# VoltageSensing.net
KiCad netlist of a schematic drawn in Altium Designer
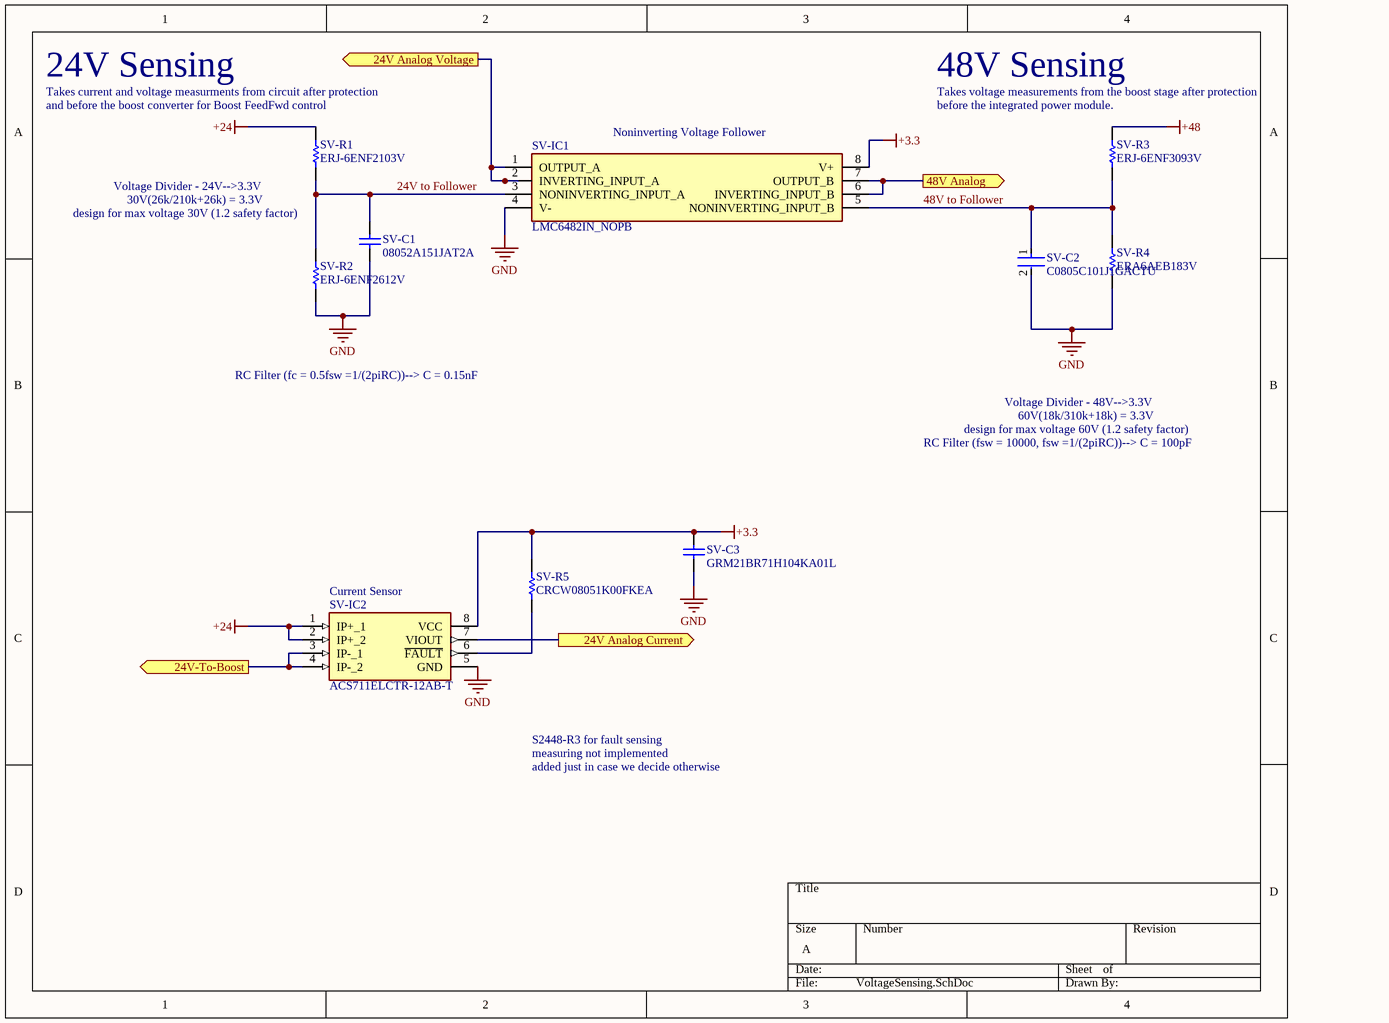
[diagram p0: VoltageSensing.SchDoc]

(export (version "E")
  (design (tool "Eeschema 10.0.6"))
  (components
    (comp (ref "SV-C1")
      (value "08052A151JAT2A")
      (footprint "CAPC2013X140X50ML20T25")
      (fields (field (name "MANUFACTURER") "AVX Interconnect / Elco"))
      (libsource (lib "Altium Content Vault") (part "CAP"))
    )
    (comp (ref "SV-C2")
      (value "C0805C101J1GACTU")
      (footprint "FP-C0805C-DN-MFG")
      (description "CAP CER 100PF 100V C0G/NP0 0805")
      (fields
        (field (name "MANUFACTURER") "KEMET")
        (field (name "OCTOPART") "https://octopart.com/c0805c101j1gactu-kemet-123666")
      )
      (libsource (lib "Altium Content Vault") (part "b4654b650e69147ec39a6b967a45e02"))
    )
    (comp (ref "SV-C3")
      (value "GRM21BR71H104KA01L")
      (footprint "CAPC2013X135X45ML10T25")
      (description "Chip Capacitor, 0.1 uF, +/- 10%, 50 V, -55 to 125 degC, 0805 (2012 Metric), RoHS, Tape and Reel")
      (fields (field (name "VOLTAGE") "50V") (field (name "TOLERANCE") "10%"))
      (libsource (lib "Altium Content Vault") (part "CAP-NP-2"))
    )
    (comp (ref "SV-IC1")
      (value "LMC6482IN_NOPB")
      (footprint "SamacSys:DIP794W53P254L959H508Q8N")
      (description "Integrated Circuit")
      (fields
        (field (name "MANUFACTURER_PART_NUMBER") "LMC6482IN/NOPB")
        (field (name "MOUSER PART NUMBER") "926-LMC6482IN/NOPB")
      )
      (libsource (lib "*") (part "LMC6482IN_NOPB"))
    )
    (comp (ref "SV-IC2")
      (value "ACS711ELCTR-12AB-T")
      (footprint "SamacSys:SOIC127P600X175-8N")
      (description "Integrated Circuit")
      (libsource (lib "*") (part "ACS711ELCTR-12AB-T"))
    )
    (comp (ref "SV-R1")
      (value "ERJ-6ENF2103V")
      (footprint "RESC2013X70X40NL20T20")
      (fields (field (name "MANUFACTURER") "Panasonic"))
      (libsource (lib "Altium Content Vault") (part "RES"))
    )
    (comp (ref "SV-R2")
      (value "ERJ-6ENF2612V")
      (footprint "RESC2013X70X40NL20T20")
      (fields (field (name "MANUFACTURER") "Panasonic"))
      (libsource (lib "Altium Content Vault") (part "RES"))
    )
    (comp (ref "SV-R3")
      (value "ERJ-6ENF3093V")
      (footprint "RESC2013X70X40NL20T20")
      (fields (field (name "MANUFACTURER") "Panasonic"))
      (libsource (lib "Altium Content Vault") (part "RES"))
    )
    (comp (ref "SV-R4")
      (value "ERA6AEB183V")
      (footprint "RESC2013X60X40LL20T25")
      (fields (field (name "MANUFACTURER") "Panasonic"))
      (libsource (lib "Altium Content Vault") (part "RES"))
    )
    (comp (ref "SV-R5")
      (value "CRCW08051K00FKEA")
      (footprint "RESC2013X50X30NL20T20")
      (fields (field (name "MANUFACTURER") "Vishay Dale"))
      (libsource (lib "Altium Content Vault") (part "RES"))
    )
  )
  (nets
    (net (code "1") (name "+3.3") (class "Default")
      (node (ref "SV-C3") (pin "2") (pinfunction "2_2") (pintype "passive"))
      (node (ref "SV-IC1") (pin "8") (pinfunction "V+_8") (pintype "passive"))
      (node (ref "SV-IC2") (pin "8") (pinfunction "VCC_8") (pintype "power_in"))
      (node (ref "SV-R5") (pin "2") (pinfunction "2_2") (pintype "passive"))
    )
    (net (code "2") (name "+24") (class "Default")
      (node (ref "SV-IC2") (pin "1") (pinfunction "IP+_1_1") (pintype "input"))
      (node (ref "SV-IC2") (pin "2") (pinfunction "IP+_2_2") (pintype "input"))
      (node (ref "SV-R1") (pin "2") (pinfunction "2_2") (pintype "passive"))
    )
    (net (code "3") (name "+48") (class "Default")
      (node (ref "SV-R3") (pin "2") (pinfunction "2_2") (pintype "passive"))
    )
    (net (code "4") (name "/24V Analog Current") (class "Default")
      (node (ref "SV-IC2") (pin "7") (pinfunction "VIOUT_7") (pintype "output"))
    )
    (net (code "5") (name "/24V Analog Voltage") (class "Default")
      (node (ref "SV-IC1") (pin "1") (pinfunction "OUTPUT_A_1") (pintype "passive"))
      (node (ref "SV-IC1") (pin "2") (pinfunction "INVERTING_INPUT_A_2") (pintype "passive"))
    )
    (net (code "6") (name "/24V to Follower") (class "Default")
      (node (ref "SV-C1") (pin "2") (pinfunction "2_2") (pintype "passive"))
      (node (ref "SV-IC1") (pin "3") (pinfunction "NONINVERTING_INPUT_A_3") (pintype "passive"))
      (node (ref "SV-R1") (pin "1") (pinfunction "1_1") (pintype "passive"))
      (node (ref "SV-R2") (pin "2") (pinfunction "2_2") (pintype "passive"))
    )
    (net (code "7") (name "/24V-To-Boost") (class "Default")
      (node (ref "SV-IC2") (pin "3") (pinfunction "IP-_1_3") (pintype "input"))
      (node (ref "SV-IC2") (pin "4") (pinfunction "IP-_2_4") (pintype "input"))
    )
    (net (code "8") (name "/48V Analog") (class "Default")
      (node (ref "SV-IC1") (pin "6") (pinfunction "INVERTING_INPUT_B_6") (pintype "passive"))
      (node (ref "SV-IC1") (pin "7") (pinfunction "OUTPUT_B_7") (pintype "passive"))
    )
    (net (code "9") (name "/48V to Follower") (class "Default")
      (node (ref "SV-C2") (pin "1") (pinfunction "1_1") (pintype "passive"))
      (node (ref "SV-IC1") (pin "5") (pinfunction "NONINVERTING_INPUT_B_5") (pintype "passive"))
      (node (ref "SV-R3") (pin "1") (pinfunction "1_1") (pintype "passive"))
      (node (ref "SV-R4") (pin "2") (pinfunction "2_2") (pintype "passive"))
    )
    (net (code "10") (name "GND") (class "Default")
      (node (ref "SV-C1") (pin "1") (pinfunction "1_1") (pintype "passive"))
      (node (ref "SV-C2") (pin "2") (pinfunction "2_2") (pintype "passive"))
      (node (ref "SV-C3") (pin "1") (pinfunction "1_1") (pintype "passive"))
      (node (ref "SV-IC1") (pin "4") (pinfunction "V-_4") (pintype "passive"))
      (node (ref "SV-IC2") (pin "5") (pinfunction "GND_5") (pintype "power_in"))
      (node (ref "SV-R2") (pin "1") (pinfunction "1_1") (pintype "passive"))
      (node (ref "SV-R4") (pin "1") (pinfunction "1_1") (pintype "passive"))
    )
    (net (code "11") (name "Net-(SV-IC2-~{FAULT})") (class "Default")
      (node (ref "SV-IC2") (pin "6") (pinfunction "~{FAULT}_6") (pintype "output"))
      (node (ref "SV-R5") (pin "1") (pinfunction "1_1") (pintype "passive"))
    )
  )
)
